# Not_gate_Transistor.net
KiCad netlist of a schematic drawn in EAGLE
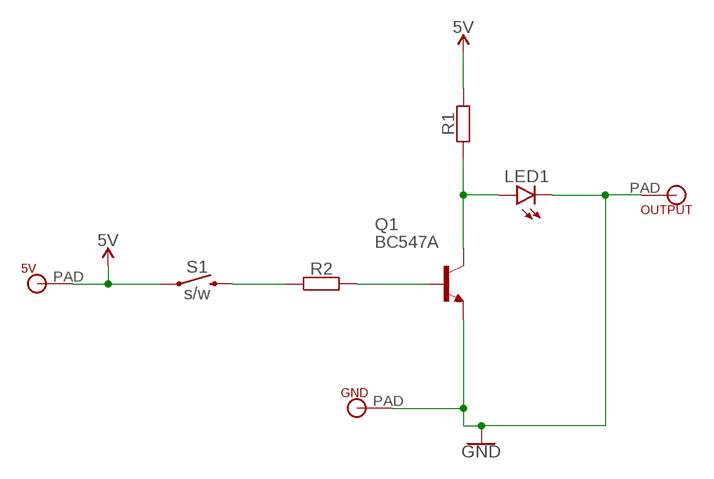
[diagram p0: schematic, sheet 1]

(export (version "E")
  (design (tool "Eeschema 10.0.6"))
  (components
    (comp (ref "5V")
      (value "5V")
      (footprint "eagle-import:MICROBIT_PAD")
      (libsource (lib "eagle-import") (part "MICROBIT_PAD"))
    )
    (comp (ref "GND")
      (value "MICROBIT_PAD")
      (footprint "eagle-import:MICROBIT_PAD")
      (libsource (lib "eagle-import") (part "MICROBIT_PAD"))
    )
    (comp (ref "LED1")
      (value "LEDCHIP-LED0805")
      (footprint "eagle-import:CHIP-LED0805")
      (libsource (lib "eagle-import") (part "LEDCHIP-LED0805"))
    )
    (comp (ref "OUTPUT")
      (value "MICROBIT_PAD")
      (footprint "eagle-import:MICROBIT_PAD")
      (libsource (lib "eagle-import") (part "MICROBIT_PAD"))
    )
    (comp (ref "Q1")
      (value "BC547A")
      (footprint "eagle-import:TO92")
      (libsource (lib "eagle-import") (part "BC547A"))
    )
    (comp (ref "R1")
      (value "RESISTOR-07")
      (footprint "eagle-import:R0207_7")
      (libsource (lib "eagle-import") (part "RESISTOR-07"))
    )
    (comp (ref "R2")
      (value "RESISTOR-07")
      (footprint "eagle-import:R0207_7")
      (libsource (lib "eagle-import") (part "RESISTOR-07"))
    )
    (comp (ref "S1")
      (value "s/w")
      (footprint "eagle-import:TACTILE_SWITCH_PTH_6.0MM")
      (libsource (lib "eagle-import") (part "MOMENTARY-SWITCH-SPST-PTH-6.0MM"))
    )
  )
  (nets
    (net (code "1") (name "5V") (class "Default")
      (node (ref "5V") (pin "PAD") (pinfunction "P$1_PAD") (pintype "bidirectional"))
      (node (ref "R1") (pin "2") (pinfunction "2_2") (pintype "passive"))
      (node (ref "S1") (pin "1") (pinfunction "1_1") (pintype "passive"))
    )
    (net (code "2") (name "GND") (class "Default")
      (node (ref "GND") (pin "PAD") (pinfunction "P$1_PAD") (pintype "bidirectional"))
      (node (ref "LED1") (pin "C") (pinfunction "C_C") (pintype "passive"))
      (node (ref "OUTPUT") (pin "PAD") (pinfunction "P$1_PAD") (pintype "bidirectional"))
      (node (ref "Q1") (pin "1") (pinfunction "E_1") (pintype "passive"))
    )
    (net (code "3") (name "Net-(Q1-B)") (class "Default")
      (node (ref "Q1") (pin "2") (pinfunction "B_2") (pintype "passive"))
      (node (ref "R2") (pin "2") (pinfunction "2_2") (pintype "passive"))
    )
    (net (code "4") (name "Net-(Q1-C)") (class "Default")
      (node (ref "LED1") (pin "A") (pinfunction "A_A") (pintype "passive"))
      (node (ref "Q1") (pin "3") (pinfunction "C_3") (pintype "passive"))
      (node (ref "R1") (pin "1") (pinfunction "1_1") (pintype "passive"))
    )
    (net (code "5") (name "Net-(S1-2)") (class "Default")
      (node (ref "R2") (pin "1") (pinfunction "1_1") (pintype "passive"))
      (node (ref "S1") (pin "3") (pinfunction "2_3") (pintype "passive"))
    )
  )
)
